# res-standalone.net
KiCad netlist of a schematic drawn in EAGLE
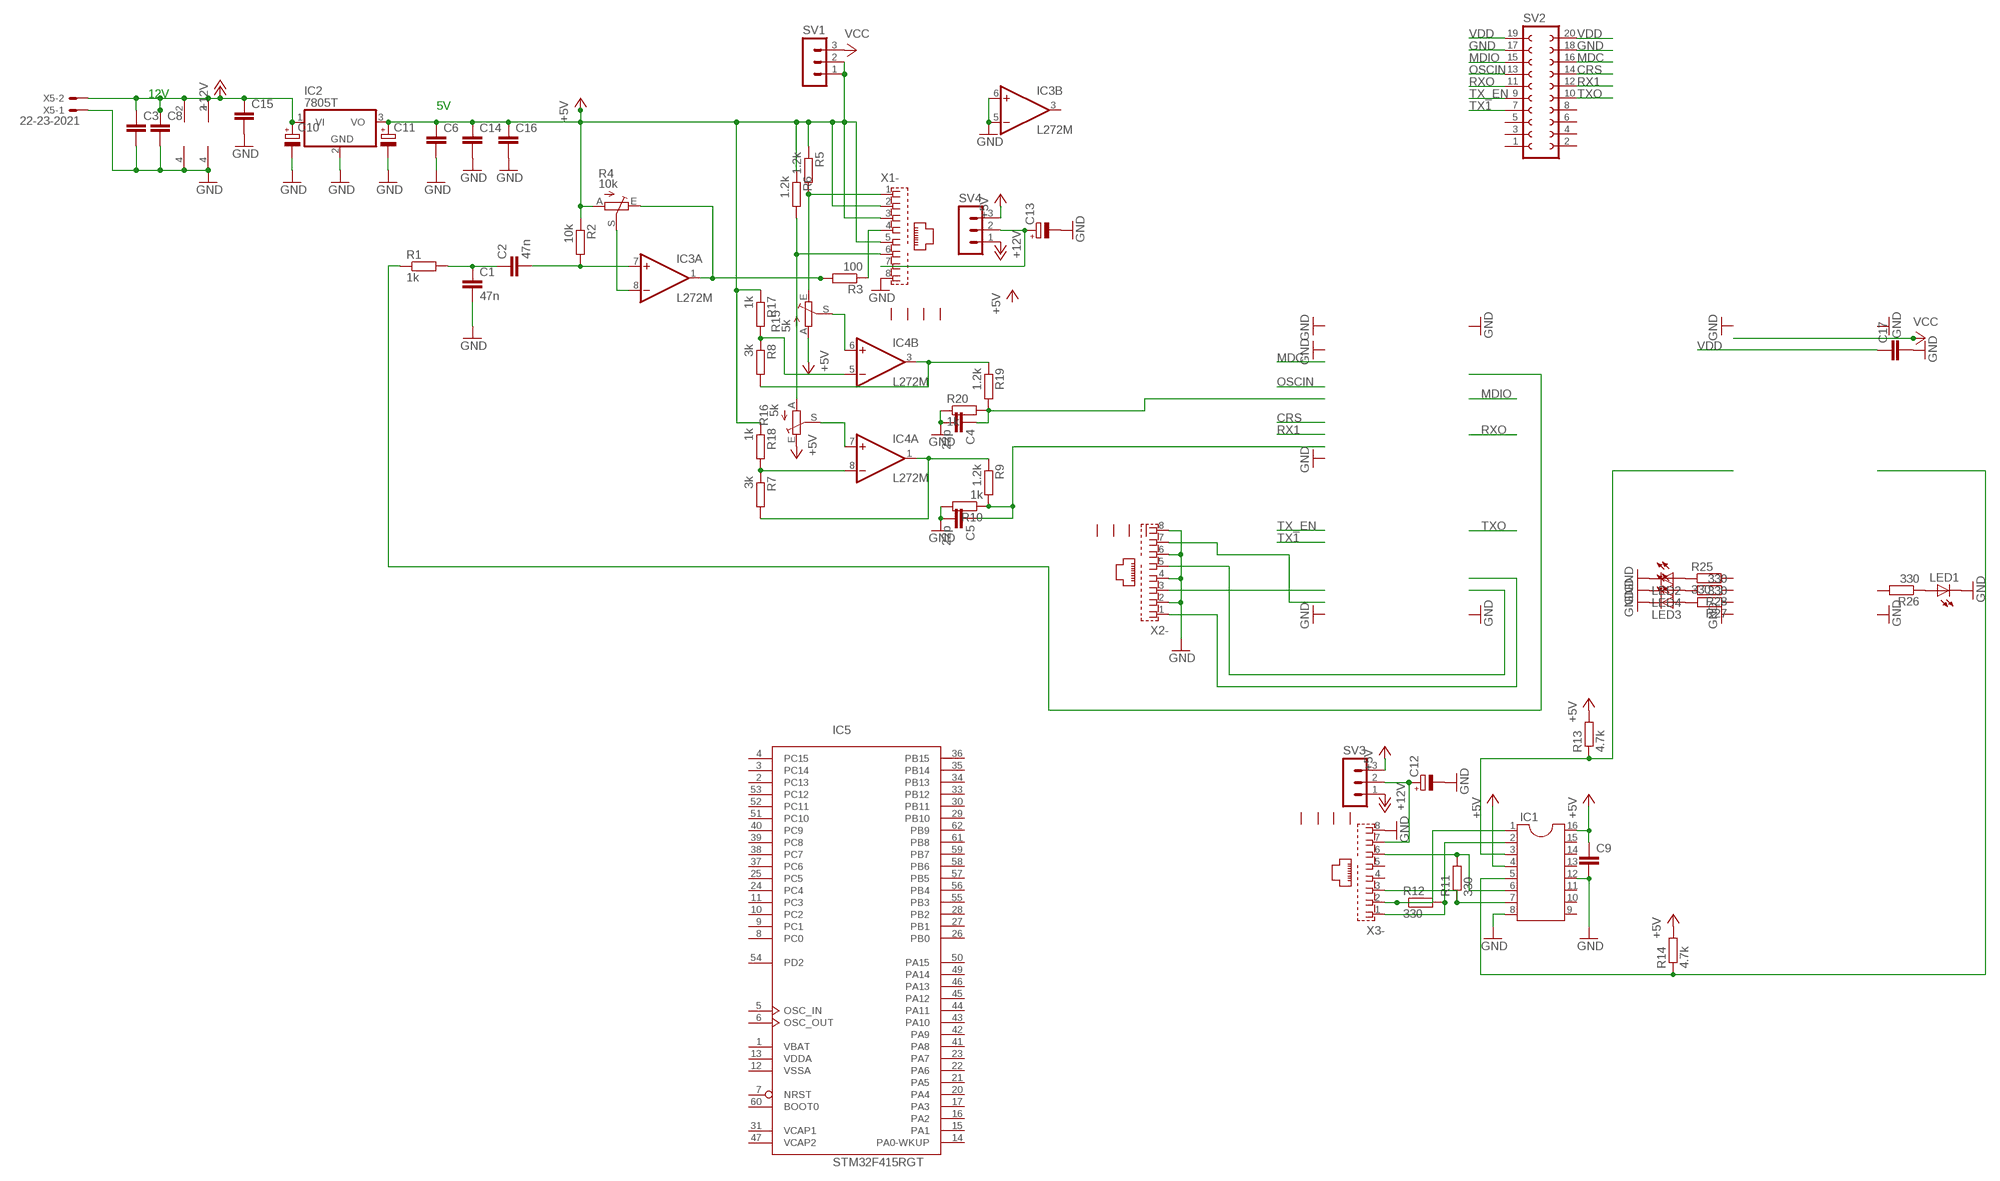
[diagram p0: schematic, sheet 1]

(export (version "E")
  (design (tool "Eeschema 10.0.6"))
  (components
    (comp (ref "C1")
      (value "47n")
      (footprint "eagle-import:C050-025X075")
      (libsource (lib "eagle-import") (part "C-EU050-025X075"))
    )
    (comp (ref "C2")
      (value "47n")
      (footprint "eagle-import:C050-025X075")
      (libsource (lib "eagle-import") (part "C-EU050-025X075"))
    )
    (comp (ref "C3")
      (value "C-EU050-025X075")
      (footprint "eagle-import:C050-025X075")
      (libsource (lib "eagle-import") (part "C-EU050-025X075"))
    )
    (comp (ref "C4")
      (value "22p")
      (footprint "eagle-import:C050-025X075")
      (libsource (lib "eagle-import") (part "C-EU050-025X075"))
    )
    (comp (ref "C5")
      (value "22p")
      (footprint "eagle-import:C050-025X075")
      (libsource (lib "eagle-import") (part "C-EU050-025X075"))
    )
    (comp (ref "C6")
      (value "C-EU050-025X075")
      (footprint "eagle-import:C050-025X075")
      (libsource (lib "eagle-import") (part "C-EU050-025X075"))
    )
    (comp (ref "C8")
      (value "C-EU050-025X075")
      (footprint "eagle-import:C050-025X075")
      (libsource (lib "eagle-import") (part "C-EU050-025X075"))
    )
    (comp (ref "C9")
      (value "C-EU050-025X075")
      (footprint "eagle-import:C050-025X075")
      (libsource (lib "eagle-import") (part "C-EU050-025X075"))
    )
    (comp (ref "C10")
      (value "CPOL-EUE2.5-5")
      (footprint "eagle-import:E2,5-5")
      (libsource (lib "eagle-import") (part "CPOL-EUE2.5-5"))
    )
    (comp (ref "C11")
      (value "CPOL-EUE2.5-5")
      (footprint "eagle-import:E2,5-5")
      (libsource (lib "eagle-import") (part "CPOL-EUE2.5-5"))
    )
    (comp (ref "C12")
      (value "CPOL-EUE2.5-5")
      (footprint "eagle-import:E2,5-5")
      (libsource (lib "eagle-import") (part "CPOL-EUE2.5-5"))
    )
    (comp (ref "C13")
      (value "CPOL-EUE2.5-5")
      (footprint "eagle-import:E2,5-5")
      (libsource (lib "eagle-import") (part "CPOL-EUE2.5-5"))
    )
    (comp (ref "C14")
      (value "C-EU050-025X075")
      (footprint "eagle-import:C050-025X075")
      (libsource (lib "eagle-import") (part "C-EU050-025X075"))
    )
    (comp (ref "C15")
      (value "C-EU050-025X075")
      (footprint "eagle-import:C050-025X075")
      (libsource (lib "eagle-import") (part "C-EU050-025X075"))
    )
    (comp (ref "C16")
      (value "C-EU050-025X075")
      (footprint "eagle-import:C050-025X075")
      (libsource (lib "eagle-import") (part "C-EU050-025X075"))
    )
    (comp (ref "C17")
      (value "C-EU050-025X075")
      (footprint "eagle-import:C050-025X075")
      (libsource (lib "eagle-import") (part "C-EU050-025X075"))
    )
    (comp (ref "IC1")
      (value "DIL16")
      (footprint "eagle-import:DIL16")
      (libsource (lib "eagle-import") (part "DIL16"))
    )
    (comp (ref "IC2")
      (value "7805T")
      (footprint "eagle-import:TO220H")
      (libsource (lib "eagle-import") (part "78T05"))
    )
    (comp (ref "IC3")
      (value "L272M")
      (footprint "eagle-import:DIL08")
      (libsource (lib "eagle-import") (part "L272M"))
    )
    (comp (ref "IC4")
      (value "L272M")
      (footprint "eagle-import:DIL08")
      (libsource (lib "eagle-import") (part "L272M"))
    )
    (comp (ref "IC5")
      (value "STM32F415RGT")
      (footprint "eagle-import:LQFP64")
      (libsource (lib "eagle-import") (part "STM32F415RTG"))
    )
    (comp (ref "LED1")
      (value "LED3MM")
      (footprint "eagle-import:LED3MM")
      (libsource (lib "eagle-import") (part "LED3MM"))
    )
    (comp (ref "LED2")
      (value "LED3MM")
      (footprint "eagle-import:LED3MM")
      (libsource (lib "eagle-import") (part "LED3MM"))
    )
    (comp (ref "LED3")
      (value "LED3MM")
      (footprint "eagle-import:LED3MM")
      (libsource (lib "eagle-import") (part "LED3MM"))
    )
    (comp (ref "LED4")
      (value "LED3MM")
      (footprint "eagle-import:LED3MM")
      (libsource (lib "eagle-import") (part "LED3MM"))
    )
    (comp (ref "R1")
      (value "1k")
      (footprint "eagle-import:0204_7")
      (libsource (lib "eagle-import") (part "R-EU_0204/7"))
    )
    (comp (ref "R2")
      (value "10k")
      (footprint "eagle-import:0204_7")
      (libsource (lib "eagle-import") (part "R-EU_0204/7"))
    )
    (comp (ref "R3")
      (value "100")
      (footprint "eagle-import:0204_7")
      (libsource (lib "eagle-import") (part "R-EU_0204/7"))
    )
    (comp (ref "R4")
      (value "10k")
      (footprint "eagle-import:CA6V")
      (libsource (lib "eagle-import") (part "TRIM_EU-CA6V"))
    )
    (comp (ref "R5")
      (value "1.2k")
      (footprint "eagle-import:0204_7")
      (libsource (lib "eagle-import") (part "R-EU_0204/7"))
    )
    (comp (ref "R6")
      (value "1.2k")
      (footprint "eagle-import:0204_7")
      (libsource (lib "eagle-import") (part "R-EU_0204/7"))
    )
    (comp (ref "R7")
      (value "3k")
      (footprint "eagle-import:0204_7")
      (libsource (lib "eagle-import") (part "R-EU_0204/7"))
    )
    (comp (ref "R8")
      (value "3k")
      (footprint "eagle-import:0204_7")
      (libsource (lib "eagle-import") (part "R-EU_0204/7"))
    )
    (comp (ref "R9")
      (value "1.2k")
      (footprint "eagle-import:0204_7")
      (libsource (lib "eagle-import") (part "R-EU_0204/7"))
    )
    (comp (ref "R10")
      (value "1k")
      (footprint "eagle-import:0204_7")
      (libsource (lib "eagle-import") (part "R-EU_0204/7"))
    )
    (comp (ref "R11")
      (value "330")
      (footprint "eagle-import:0204_7")
      (libsource (lib "eagle-import") (part "R-EU_0204/7"))
    )
    (comp (ref "R12")
      (value "330")
      (footprint "eagle-import:0204_7")
      (libsource (lib "eagle-import") (part "R-EU_0204/7"))
    )
    (comp (ref "R13")
      (value "4.7k")
      (footprint "eagle-import:0204_7")
      (libsource (lib "eagle-import") (part "R-EU_0204/7"))
    )
    (comp (ref "R14")
      (value "4.7k")
      (footprint "eagle-import:0204_7")
      (libsource (lib "eagle-import") (part "R-EU_0204/7"))
    )
    (comp (ref "R15")
      (value "5k")
      (footprint "eagle-import:CA6V")
      (libsource (lib "eagle-import") (part "TRIM_EU-CA6V"))
    )
    (comp (ref "R16")
      (value "5k")
      (footprint "eagle-import:CA6V")
      (libsource (lib "eagle-import") (part "TRIM_EU-CA6V"))
    )
    (comp (ref "R17")
      (value "1k")
      (footprint "eagle-import:0204_7")
      (libsource (lib "eagle-import") (part "R-EU_0204/7"))
    )
    (comp (ref "R18")
      (value "1k")
      (footprint "eagle-import:0204_7")
      (libsource (lib "eagle-import") (part "R-EU_0204/7"))
    )
    (comp (ref "R19")
      (value "1.2k")
      (footprint "eagle-import:0204_7")
      (libsource (lib "eagle-import") (part "R-EU_0204/7"))
    )
    (comp (ref "R20")
      (value "1k")
      (footprint "eagle-import:0204_7")
      (libsource (lib "eagle-import") (part "R-EU_0204/7"))
    )
    (comp (ref "R25")
      (value "330")
      (footprint "eagle-import:0204_7")
      (libsource (lib "eagle-import") (part "R-EU_0204/7"))
    )
    (comp (ref "R26")
      (value "330")
      (footprint "eagle-import:0204_7")
      (libsource (lib "eagle-import") (part "R-EU_0204/7"))
    )
    (comp (ref "R27")
      (value "330")
      (footprint "eagle-import:0204_7")
      (libsource (lib "eagle-import") (part "R-EU_0204/7"))
    )
    (comp (ref "R28")
      (value "330")
      (footprint "eagle-import:0204_7")
      (libsource (lib "eagle-import") (part "R-EU_0204/7"))
    )
    (comp (ref "SV1")
      (value "MA03-1")
      (footprint "eagle-import:MA03-1")
      (libsource (lib "eagle-import") (part "MA03-1"))
    )
    (comp (ref "SV2")
      (value "FE10-2W")
      (footprint "eagle-import:FE10-2W")
      (libsource (lib "eagle-import") (part "FE10-2W"))
    )
    (comp (ref "SV3")
      (value "MA03-1")
      (footprint "eagle-import:MA03-1")
      (libsource (lib "eagle-import") (part "MA03-1"))
    )
    (comp (ref "SV4")
      (value "MA03-1")
      (footprint "eagle-import:MA03-1")
      (libsource (lib "eagle-import") (part "MA03-1"))
    )
    (comp (ref "X1")
      (value "RJ45")
      (footprint "eagle-import:RJ45")
      (libsource (lib "eagle-import") (part "RJ45"))
    )
    (comp (ref "X2")
      (value "RJ45")
      (footprint "eagle-import:RJ45")
      (libsource (lib "eagle-import") (part "RJ45"))
    )
    (comp (ref "X3")
      (value "RJ45")
      (footprint "eagle-import:RJ45")
      (libsource (lib "eagle-import") (part "RJ45"))
    )
    (comp (ref "X5")
      (value "22-23-2021")
      (footprint "eagle-import:22-23-2021")
      (fields (field (name "MF") "MOLEX"))
      (libsource (lib "eagle-import") (part "22-23-2021"))
    )
  )
  (nets
    (net (code "1") (name "+5V") (class "Default")
      (node (ref "C11") (pin "+") (pinfunction "+_+") (pintype "passive"))
      (node (ref "C14") (pin "1") (pinfunction "1_1") (pintype "passive"))
      (node (ref "C16") (pin "1") (pinfunction "1_1") (pintype "passive"))
      (node (ref "C6") (pin "1") (pinfunction "1_1") (pintype "passive"))
      (node (ref "C9") (pin "1") (pinfunction "1_1") (pintype "passive"))
      (node (ref "IC1") (pin "16") (pinfunction "16_16") (pintype "passive"))
      (node (ref "IC1") (pin "4") (pinfunction "4_4") (pintype "passive"))
      (node (ref "IC2") (pin "3") (pinfunction "VO_3") (pintype "passive"))
      (node (ref "R13") (pin "2") (pinfunction "2_2") (pintype "passive"))
      (node (ref "R14") (pin "2") (pinfunction "2_2") (pintype "passive"))
      (node (ref "R15") (pin "A") (pinfunction "A_A") (pintype "passive"))
      (node (ref "R16") (pin "E") (pinfunction "E_E") (pintype "passive"))
      (node (ref "R17") (pin "1") (pinfunction "1_1") (pintype "passive"))
      (node (ref "R18") (pin "1") (pinfunction "1_1") (pintype "passive"))
      (node (ref "R2") (pin "1") (pinfunction "1_1") (pintype "passive"))
      (node (ref "R4") (pin "A") (pinfunction "A_A") (pintype "passive"))
      (node (ref "R5") (pin "1") (pinfunction "1_1") (pintype "passive"))
      (node (ref "R6") (pin "1") (pinfunction "1_1") (pintype "passive"))
      (node (ref "SV1") (pin "1") (pinfunction "1_1") (pintype "passive"))
      (node (ref "SV1") (pin "2") (pinfunction "2_2") (pintype "passive"))
      (node (ref "SV3") (pin "3") (pinfunction "3_3") (pintype "passive"))
      (node (ref "SV4") (pin "3") (pinfunction "3_3") (pintype "passive"))
      (node (ref "X1") (pin "2") (pinfunction "2_2") (pintype "passive"))
      (node (ref "X1") (pin "3") (pinfunction "3_3") (pintype "passive"))
      (node (ref "X1") (pin "5") (pinfunction "5_5") (pintype "passive"))
    )
    (net (code "2") (name "+12V") (class "Default")
      (node (ref "C10") (pin "+") (pinfunction "+_+") (pintype "passive"))
      (node (ref "C15") (pin "1") (pinfunction "1_1") (pintype "passive"))
      (node (ref "C3") (pin "1") (pinfunction "1_1") (pintype "passive"))
      (node (ref "C8") (pin "1") (pinfunction "1_1") (pintype "passive"))
      (node (ref "IC2") (pin "1") (pinfunction "VI_1") (pintype "input"))
      (node (ref "IC3") (pin "2") (pinfunction "V+_2") (pintype "power_in"))
      (node (ref "IC4") (pin "2") (pinfunction "V+_2") (pintype "power_in"))
      (node (ref "SV3") (pin "1") (pinfunction "1_1") (pintype "passive"))
      (node (ref "SV4") (pin "1") (pinfunction "1_1") (pintype "passive"))
      (node (ref "X5") (pin "2") (pinfunction "S_2") (pintype "passive"))
    )
    (net (code "3") (name "/CRS") (class "Default")
      (node (ref "SV2") (pin "14") (pinfunction "14_14") (pintype "passive"))
    )
    (net (code "4") (name "/MDC") (class "Default")
      (node (ref "SV2") (pin "16") (pinfunction "16_16") (pintype "passive"))
    )
    (net (code "5") (name "/MDIO") (class "Default")
      (node (ref "SV2") (pin "15") (pinfunction "15_15") (pintype "passive"))
    )
    (net (code "6") (name "/OSCIN") (class "Default")
      (node (ref "SV2") (pin "13") (pinfunction "13_13") (pintype "passive"))
    )
    (net (code "7") (name "/RX1") (class "Default")
      (node (ref "SV2") (pin "12") (pinfunction "12_12") (pintype "passive"))
    )
    (net (code "8") (name "/RXO") (class "Default")
      (node (ref "SV2") (pin "11") (pinfunction "11_11") (pintype "passive"))
    )
    (net (code "9") (name "/TX1") (class "Default")
      (node (ref "SV2") (pin "7") (pinfunction "7_7") (pintype "passive"))
    )
    (net (code "10") (name "/TXO") (class "Default")
      (node (ref "SV2") (pin "10") (pinfunction "10_10") (pintype "passive"))
    )
    (net (code "11") (name "/TX_EN") (class "Default")
      (node (ref "SV2") (pin "9") (pinfunction "9_9") (pintype "passive"))
    )
    (net (code "12") (name "/VBAT") (class "Default")
      (node (ref "IC5") (pin "1") (pinfunction "VBAT_1") (pintype "power_in"))
    )
    (net (code "13") (name "/VCAP1") (class "Default")
      (node (ref "IC5") (pin "31") (pinfunction "VCAP1_31") (pintype "power_in"))
    )
    (net (code "14") (name "/VCAP2") (class "Default")
      (node (ref "IC5") (pin "47") (pinfunction "VCAP2_47") (pintype "power_in"))
    )
    (net (code "15") (name "/VDD") (class "Default")
      (node (ref "C17") (pin "1") (pinfunction "1_1") (pintype "passive"))
      (node (ref "SV2") (pin "19") (pinfunction "19_19") (pintype "passive"))
      (node (ref "SV2") (pin "20") (pinfunction "20_20") (pintype "passive"))
    )
    (net (code "16") (name "/VDDA") (class "Default")
      (node (ref "IC5") (pin "13") (pinfunction "VDDA_13") (pintype "power_in"))
    )
    (net (code "17") (name "/VSSA") (class "Default")
      (node (ref "IC5") (pin "12") (pinfunction "VSSA_12") (pintype "power_in"))
    )
    (net (code "18") (name "GND") (class "Default")
      (node (ref "C1") (pin "2") (pinfunction "2_2") (pintype "passive"))
      (node (ref "C10") (pin "-") (pinfunction "-_-") (pintype "passive"))
      (node (ref "C11") (pin "-") (pinfunction "-_-") (pintype "passive"))
      (node (ref "C12") (pin "-") (pinfunction "-_-") (pintype "passive"))
      (node (ref "C13") (pin "-") (pinfunction "-_-") (pintype "passive"))
      (node (ref "C14") (pin "2") (pinfunction "2_2") (pintype "passive"))
      (node (ref "C15") (pin "2") (pinfunction "2_2") (pintype "passive"))
      (node (ref "C16") (pin "2") (pinfunction "2_2") (pintype "passive"))
      (node (ref "C17") (pin "2") (pinfunction "2_2") (pintype "passive"))
      (node (ref "C3") (pin "2") (pinfunction "2_2") (pintype "passive"))
      (node (ref "C4") (pin "2") (pinfunction "2_2") (pintype "passive"))
      (node (ref "C5") (pin "2") (pinfunction "2_2") (pintype "passive"))
      (node (ref "C6") (pin "2") (pinfunction "2_2") (pintype "passive"))
      (node (ref "C8") (pin "2") (pinfunction "2_2") (pintype "passive"))
      (node (ref "C9") (pin "2") (pinfunction "2_2") (pintype "passive"))
      (node (ref "IC1") (pin "12") (pinfunction "12_12") (pintype "passive"))
      (node (ref "IC1") (pin "8") (pinfunction "8_8") (pintype "passive"))
      (node (ref "IC2") (pin "2") (pinfunction "GND_2") (pintype "passive"))
      (node (ref "IC3") (pin "4") (pinfunction "GND_4") (pintype "power_in"))
      (node (ref "IC3") (pin "5") (pinfunction "-IN_5") (pintype "input"))
      (node (ref "IC3") (pin "6") (pinfunction "+IN_6") (pintype "input"))
      (node (ref "IC4") (pin "4") (pinfunction "GND_4") (pintype "power_in"))
      (node (ref "LED1") (pin "K") (pinfunction "C_K") (pintype "passive"))
      (node (ref "LED2") (pin "K") (pinfunction "C_K") (pintype "passive"))
      (node (ref "LED3") (pin "K") (pinfunction "C_K") (pintype "passive"))
      (node (ref "LED4") (pin "K") (pinfunction "C_K") (pintype "passive"))
      (node (ref "R10") (pin "2") (pinfunction "2_2") (pintype "passive"))
      (node (ref "R20") (pin "1") (pinfunction "1_1") (pintype "passive"))
      (node (ref "SV2") (pin "17") (pinfunction "17_17") (pintype "passive"))
      (node (ref "SV2") (pin "18") (pinfunction "18_18") (pintype "passive"))
      (node (ref "X1") (pin "8") (pinfunction "8_8") (pintype "passive"))
      (node (ref "X2") (pin "2") (pinfunction "2_2") (pintype "passive"))
      (node (ref "X2") (pin "4") (pinfunction "4_4") (pintype "passive"))
      (node (ref "X2") (pin "6") (pinfunction "6_6") (pintype "passive"))
      (node (ref "X2") (pin "8") (pinfunction "8_8") (pintype "passive"))
      (node (ref "X3") (pin "8") (pinfunction "8_8") (pintype "passive"))
      (node (ref "X5") (pin "1") (pinfunction "S_1") (pintype "passive"))
    )
    (net (code "19") (name "Net-(C1-Pad1)") (class "Default")
      (node (ref "C1") (pin "1") (pinfunction "1_1") (pintype "passive"))
      (node (ref "C2") (pin "1") (pinfunction "1_1") (pintype "passive"))
      (node (ref "R1") (pin "2") (pinfunction "2_2") (pintype "passive"))
    )
    (net (code "20") (name "Net-(C4-Pad1)") (class "Default")
      (node (ref "C4") (pin "1") (pinfunction "1_1") (pintype "passive"))
      (node (ref "R19") (pin "2") (pinfunction "2_2") (pintype "passive"))
      (node (ref "R20") (pin "2") (pinfunction "2_2") (pintype "passive"))
    )
    (net (code "21") (name "Net-(C5-Pad1)") (class "Default")
      (node (ref "C5") (pin "1") (pinfunction "1_1") (pintype "passive"))
      (node (ref "R10") (pin "1") (pinfunction "1_1") (pintype "passive"))
      (node (ref "R9") (pin "2") (pinfunction "2_2") (pintype "passive"))
    )
    (net (code "22") (name "Net-(C12-Pad+)") (class "Default")
      (node (ref "C12") (pin "+") (pinfunction "+_+") (pintype "passive"))
      (node (ref "SV3") (pin "2") (pinfunction "2_2") (pintype "passive"))
      (node (ref "X3") (pin "7") (pinfunction "7_7") (pintype "passive"))
    )
    (net (code "23") (name "Net-(C13-Pad+)") (class "Default")
      (node (ref "C13") (pin "+") (pinfunction "+_+") (pintype "passive"))
      (node (ref "SV4") (pin "2") (pinfunction "2_2") (pintype "passive"))
      (node (ref "X1") (pin "7") (pinfunction "7_7") (pintype "passive"))
    )
    (net (code "24") (name "Net-(IC1-Pad1)") (class "Default")
      (node (ref "IC1") (pin "1") (pinfunction "1_1") (pintype "passive"))
      (node (ref "R12") (pin "1") (pinfunction "1_1") (pintype "passive"))
      (node (ref "X3") (pin "2") (pinfunction "2_2") (pintype "passive"))
    )
    (net (code "25") (name "Net-(IC1-Pad2)") (class "Default")
      (node (ref "IC1") (pin "2") (pinfunction "2_2") (pintype "passive"))
      (node (ref "R12") (pin "2") (pinfunction "2_2") (pintype "passive"))
      (node (ref "X3") (pin "1") (pinfunction "1_1") (pintype "passive"))
    )
    (net (code "26") (name "Net-(IC1-Pad3)") (class "Default")
      (node (ref "IC1") (pin "3") (pinfunction "3_3") (pintype "passive"))
      (node (ref "R13") (pin "1") (pinfunction "1_1") (pintype "passive"))
    )
    (net (code "27") (name "Net-(IC1-Pad5)") (class "Default")
      (node (ref "IC1") (pin "5") (pinfunction "5_5") (pintype "passive"))
      (node (ref "R14") (pin "1") (pinfunction "1_1") (pintype "passive"))
    )
    (net (code "28") (name "Net-(IC1-Pad6)") (class "Default")
      (node (ref "IC1") (pin "6") (pinfunction "6_6") (pintype "passive"))
      (node (ref "R11") (pin "2") (pinfunction "2_2") (pintype "passive"))
      (node (ref "X3") (pin "6") (pinfunction "6_6") (pintype "passive"))
    )
    (net (code "29") (name "Net-(IC1-Pad7)") (class "Default")
      (node (ref "IC1") (pin "7") (pinfunction "7_7") (pintype "passive"))
      (node (ref "R11") (pin "1") (pinfunction "1_1") (pintype "passive"))
      (node (ref "X3") (pin "3") (pinfunction "3_3") (pintype "passive"))
    )
    (net (code "30") (name "Net-(IC3A-+IN)") (class "Default")
      (node (ref "C2") (pin "2") (pinfunction "2_2") (pintype "passive"))
      (node (ref "IC3") (pin "7") (pinfunction "+IN_7") (pintype "input"))
      (node (ref "R2") (pin "2") (pinfunction "2_2") (pintype "passive"))
    )
    (net (code "31") (name "Net-(IC3A--IN)") (class "Default")
      (node (ref "IC3") (pin "8") (pinfunction "-IN_8") (pintype "input"))
      (node (ref "R4") (pin "S") (pinfunction "S_S") (pintype "passive"))
    )
    (net (code "32") (name "Net-(IC3A-OUT)") (class "Default")
      (node (ref "IC3") (pin "1") (pinfunction "OUT_1") (pintype "output"))
      (node (ref "R3") (pin "2") (pinfunction "2_2") (pintype "passive"))
      (node (ref "R4") (pin "E") (pinfunction "E_E") (pintype "passive"))
    )
    (net (code "33") (name "Net-(IC4A-+IN)") (class "Default")
      (node (ref "IC4") (pin "7") (pinfunction "+IN_7") (pintype "input"))
      (node (ref "R16") (pin "S") (pinfunction "S_S") (pintype "passive"))
    )
    (net (code "34") (name "Net-(IC4A--IN)") (class "Default")
      (node (ref "IC4") (pin "8") (pinfunction "-IN_8") (pintype "input"))
      (node (ref "R18") (pin "2") (pinfunction "2_2") (pintype "passive"))
      (node (ref "R7") (pin "1") (pinfunction "1_1") (pintype "passive"))
    )
    (net (code "35") (name "Net-(IC4A-OUT)") (class "Default")
      (node (ref "IC4") (pin "1") (pinfunction "OUT_1") (pintype "output"))
      (node (ref "R7") (pin "2") (pinfunction "2_2") (pintype "passive"))
      (node (ref "R9") (pin "1") (pinfunction "1_1") (pintype "passive"))
    )
    (net (code "36") (name "Net-(IC4B-+IN)") (class "Default")
      (node (ref "IC4") (pin "6") (pinfunction "+IN_6") (pintype "input"))
      (node (ref "R15") (pin "S") (pinfunction "S_S") (pintype "passive"))
    )
    (net (code "37") (name "Net-(IC4B--IN)") (class "Default")
      (node (ref "IC4") (pin "5") (pinfunction "-IN_5") (pintype "input"))
      (node (ref "R17") (pin "2") (pinfunction "2_2") (pintype "passive"))
      (node (ref "R8") (pin "1") (pinfunction "1_1") (pintype "passive"))
    )
    (net (code "38") (name "Net-(IC4B-OUT)") (class "Default")
      (node (ref "IC4") (pin "3") (pinfunction "OUT_3") (pintype "output"))
      (node (ref "R19") (pin "1") (pinfunction "1_1") (pintype "passive"))
      (node (ref "R8") (pin "2") (pinfunction "2_2") (pintype "passive"))
    )
    (net (code "39") (name "Net-(LED1-PadA)") (class "Default")
      (node (ref "LED1") (pin "A") (pinfunction "A_A") (pintype "passive"))
      (node (ref "R26") (pin "1") (pinfunction "1_1") (pintype "passive"))
    )
    (net (code "40") (name "Net-(LED2-PadA)") (class "Default")
      (node (ref "LED2") (pin "A") (pinfunction "A_A") (pintype "passive"))
      (node (ref "R25") (pin "1") (pinfunction "1_1") (pintype "passive"))
    )
    (net (code "41") (name "Net-(LED3-PadA)") (class "Default")
      (node (ref "LED3") (pin "A") (pinfunction "A_A") (pintype "passive"))
      (node (ref "R27") (pin "2") (pinfunction "2_2") (pintype "passive"))
    )
    (net (code "42") (name "Net-(LED4-PadA)") (class "Default")
      (node (ref "LED4") (pin "A") (pinfunction "A_A") (pintype "passive"))
      (node (ref "R28") (pin "2") (pinfunction "2_2") (pintype "passive"))
    )
    (net (code "43") (name "Net-(R3-Pad1)") (class "Default")
      (node (ref "R3") (pin "1") (pinfunction "1_1") (pintype "passive"))
      (node (ref "X1") (pin "4") (pinfunction "4_4") (pintype "passive"))
    )
    (net (code "44") (name "Net-(R15-PadE)") (class "Default")
      (node (ref "R15") (pin "E") (pinfunction "E_E") (pintype "passive"))
      (node (ref "R5") (pin "2") (pinfunction "2_2") (pintype "passive"))
      (node (ref "X1") (pin "1") (pinfunction "1_1") (pintype "passive"))
    )
    (net (code "45") (name "Net-(R16-PadA)") (class "Default")
      (node (ref "R16") (pin "A") (pinfunction "A_A") (pintype "passive"))
      (node (ref "R6") (pin "2") (pinfunction "2_2") (pintype "passive"))
      (node (ref "X1") (pin "6") (pinfunction "6_6") (pintype "passive"))
    )
    (net (code "46") (name "VCC") (class "Default")
      (node (ref "SV1") (pin "3") (pinfunction "3_3") (pintype "passive"))
    )
    (net (code "47") (name "unconnected-(IC1-Pad9)") (class "Default")
      (node (ref "IC1") (pin "9") (pinfunction "9_9") (pintype "passive"))
    )
    (net (code "48") (name "unconnected-(IC1-Pad10)") (class "Default")
      (node (ref "IC1") (pin "10") (pinfunction "10_10") (pintype "passive"))
    )
    (net (code "49") (name "unconnected-(IC1-Pad11)") (class "Default")
      (node (ref "IC1") (pin "11") (pinfunction "11_11") (pintype "passive"))
    )
    (net (code "50") (name "unconnected-(IC1-Pad13)") (class "Default")
      (node (ref "IC1") (pin "13") (pinfunction "13_13") (pintype "passive"))
    )
    (net (code "51") (name "unconnected-(IC1-Pad14)") (class "Default")
      (node (ref "IC1") (pin "14") (pinfunction "14_14") (pintype "passive"))
    )
    (net (code "52") (name "unconnected-(IC1-Pad15)") (class "Default")
      (node (ref "IC1") (pin "15") (pinfunction "15_15") (pintype "passive"))
    )
    (net (code "53") (name "unconnected-(IC3B-OUT-Pad3)") (class "Default")
      (node (ref "IC3") (pin "3") (pinfunction "OUT_3") (pintype "output"))
    )
    (net (code "54") (name "unconnected-(IC5A-BOOT0-Pad60)") (class "Default")
      (node (ref "IC5") (pin "60") (pinfunction "BOOT0_60") (pintype "input"))
    )
    (net (code "55") (name "unconnected-(IC5A-NRST-Pad7)") (class "Default")
      (node (ref "IC5") (pin "7") (pinfunction "NRST_7") (pintype "bidirectional"))
    )
    (net (code "56") (name "unconnected-(IC5A-OSC_IN-Pad5)") (class "Default")
      (node (ref "IC5") (pin "5") (pinfunction "OSC_IN_5") (pintype "bidirectional"))
    )
    (net (code "57") (name "unconnected-(IC5A-OSC_OUT-Pad6)") (class "Default")
      (node (ref "IC5") (pin "6") (pinfunction "OSC_OUT_6") (pintype "bidirectional"))
    )
    (net (code "58") (name "unconnected-(IC5A-PA0-WKUP-Pad14)") (class "Default")
      (node (ref "IC5") (pin "14") (pinfunction "PA0-WKUP_14") (pintype "bidirectional"))
    )
    (net (code "59") (name "unconnected-(IC5A-PA1-Pad15)") (class "Default")
      (node (ref "IC5") (pin "15") (pinfunction "PA1_15") (pintype "bidirectional"))
    )
    (net (code "60") (name "unconnected-(IC5A-PA2-Pad16)") (class "Default")
      (node (ref "IC5") (pin "16") (pinfunction "PA2_16") (pintype "bidirectional"))
    )
    (net (code "61") (name "unconnected-(IC5A-PA3-Pad17)") (class "Default")
      (node (ref "IC5") (pin "17") (pinfunction "PA3_17") (pintype "bidirectional"))
    )
    (net (code "62") (name "unconnected-(IC5A-PA4-Pad20)") (class "Default")
      (node (ref "IC5") (pin "20") (pinfunction "PA4_20") (pintype "bidirectional"))
    )
    (net (code "63") (name "unconnected-(IC5A-PA5-Pad21)") (class "Default")
      (node (ref "IC5") (pin "21") (pinfunction "PA5_21") (pintype "bidirectional"))
    )
    (net (code "64") (name "unconnected-(IC5A-PA6-Pad22)") (class "Default")
      (node (ref "IC5") (pin "22") (pinfunction "PA6_22") (pintype "bidirectional"))
    )
    (net (code "65") (name "unconnected-(IC5A-PA7-Pad23)") (class "Default")
      (node (ref "IC5") (pin "23") (pinfunction "PA7_23") (pintype "bidirectional"))
    )
    (net (code "66") (name "unconnected-(IC5A-PA8-Pad41)") (class "Default")
      (node (ref "IC5") (pin "41") (pinfunction "PA8_41") (pintype "bidirectional"))
    )
    (net (code "67") (name "unconnected-(IC5A-PA9-Pad42)") (class "Default")
      (node (ref "IC5") (pin "42") (pinfunction "PA9_42") (pintype "bidirectional"))
    )
    (net (code "68") (name "unconnected-(IC5A-PA10-Pad43)") (class "Default")
      (node (ref "IC5") (pin "43") (pinfunction "PA10_43") (pintype "bidirectional"))
    )
    (net (code "69") (name "unconnected-(IC5A-PA11-Pad44)") (class "Default")
      (node (ref "IC5") (pin "44") (pinfunction "PA11_44") (pintype "bidirectional"))
    )
    (net (code "70") (name "unconnected-(IC5A-PA12-Pad45)") (class "Default")
      (node (ref "IC5") (pin "45") (pinfunction "PA12_45") (pintype "bidirectional"))
    )
    (net (code "71") (name "unconnected-(IC5A-PA13-Pad46)") (class "Default")
      (node (ref "IC5") (pin "46") (pinfunction "PA13_46") (pintype "bidirectional"))
    )
    (net (code "72") (name "unconnected-(IC5A-PA14-Pad49)") (class "Default")
      (node (ref "IC5") (pin "49") (pinfunction "PA14_49") (pintype "bidirectional"))
    )
    (net (code "73") (name "unconnected-(IC5A-PA15-Pad50)") (class "Default")
      (node (ref "IC5") (pin "50") (pinfunction "PA15_50") (pintype "bidirectional"))
    )
    (net (code "74") (name "unconnected-(IC5A-PB0-Pad26)") (class "Default")
      (node (ref "IC5") (pin "26") (pinfunction "PB0_26") (pintype "bidirectional"))
    )
    (net (code "75") (name "unconnected-(IC5A-PB1-Pad27)") (class "Default")
      (node (ref "IC5") (pin "27") (pinfunction "PB1_27") (pintype "bidirectional"))
    )
    (net (code "76") (name "unconnected-(IC5A-PB2-Pad28)") (class "Default")
      (node (ref "IC5") (pin "28") (pinfunction "PB2_28") (pintype "bidirectional"))
    )
    (net (code "77") (name "unconnected-(IC5A-PB3-Pad55)") (class "Default")
      (node (ref "IC5") (pin "55") (pinfunction "PB3_55") (pintype "bidirectional"))
    )
    (net (code "78") (name "unconnected-(IC5A-PB4-Pad56)") (class "Default")
      (node (ref "IC5") (pin "56") (pinfunction "PB4_56") (pintype "bidirectional"))
    )
    (net (code "79") (name "unconnected-(IC5A-PB5-Pad57)") (class "Default")
      (node (ref "IC5") (pin "57") (pinfunction "PB5_57") (pintype "bidirectional"))
    )
    (net (code "80") (name "unconnected-(IC5A-PB6-Pad58)") (class "Default")
      (node (ref "IC5") (pin "58") (pinfunction "PB6_58") (pintype "bidirectional"))
    )
    (net (code "81") (name "unconnected-(IC5A-PB7-Pad59)") (class "Default")
      (node (ref "IC5") (pin "59") (pinfunction "PB7_59") (pintype "bidirectional"))
    )
    (net (code "82") (name "unconnected-(IC5A-PB8-Pad61)") (class "Default")
      (node (ref "IC5") (pin "61") (pinfunction "PB8_61") (pintype "bidirectional"))
    )
    (net (code "83") (name "unconnected-(IC5A-PB9-Pad62)") (class "Default")
      (node (ref "IC5") (pin "62") (pinfunction "PB9_62") (pintype "bidirectional"))
    )
    (net (code "84") (name "unconnected-(IC5A-PB10-Pad29)") (class "Default")
      (node (ref "IC5") (pin "29") (pinfunction "PB10_29") (pintype "bidirectional"))
    )
    (net (code "85") (name "unconnected-(IC5A-PB11-Pad30)") (class "Default")
      (node (ref "IC5") (pin "30") (pinfunction "PB11_30") (pintype "bidirectional"))
    )
    (net (code "86") (name "unconnected-(IC5A-PB12-Pad33)") (class "Default")
      (node (ref "IC5") (pin "33") (pinfunction "PB12_33") (pintype "bidirectional"))
    )
    (net (code "87") (name "unconnected-(IC5A-PB13-Pad34)") (class "Default")
      (node (ref "IC5") (pin "34") (pinfunction "PB13_34") (pintype "bidirectional"))
    )
    (net (code "88") (name "unconnected-(IC5A-PB14-Pad35)") (class "Default")
      (node (ref "IC5") (pin "35") (pinfunction "PB14_35") (pintype "bidirectional"))
    )
    (net (code "89") (name "unconnected-(IC5A-PB15-Pad36)") (class "Default")
      (node (ref "IC5") (pin "36") (pinfunction "PB15_36") (pintype "bidirectional"))
    )
    (net (code "90") (name "unconnected-(IC5A-PC0-Pad8)") (class "Default")
      (node (ref "IC5") (pin "8") (pinfunction "PC0_8") (pintype "bidirectional"))
    )
    (net (code "91") (name "unconnected-(IC5A-PC1-Pad9)") (class "Default")
      (node (ref "IC5") (pin "9") (pinfunction "PC1_9") (pintype "bidirectional"))
    )
    (net (code "92") (name "unconnected-(IC5A-PC2-Pad10)") (class "Default")
      (node (ref "IC5") (pin "10") (pinfunction "PC2_10") (pintype "bidirectional"))
    )
    (net (code "93") (name "unconnected-(IC5A-PC3-Pad11)") (class "Default")
      (node (ref "IC5") (pin "11") (pinfunction "PC3_11") (pintype "bidirectional"))
    )
    (net (code "94") (name "unconnected-(IC5A-PC4-Pad24)") (class "Default")
      (node (ref "IC5") (pin "24") (pinfunction "PC4_24") (pintype "bidirectional"))
    )
    (net (code "95") (name "unconnected-(IC5A-PC5-Pad25)") (class "Default")
      (node (ref "IC5") (pin "25") (pinfunction "PC5_25") (pintype "bidirectional"))
    )
    (net (code "96") (name "unconnected-(IC5A-PC6-Pad37)") (class "Default")
      (node (ref "IC5") (pin "37") (pinfunction "PC6_37") (pintype "bidirectional"))
    )
    (net (code "97") (name "unconnected-(IC5A-PC7-Pad38)") (class "Default")
      (node (ref "IC5") (pin "38") (pinfunction "PC7_38") (pintype "bidirectional"))
    )
    (net (code "98") (name "unconnected-(IC5A-PC8-Pad39)") (class "Default")
      (node (ref "IC5") (pin "39") (pinfunction "PC8_39") (pintype "bidirectional"))
    )
    (net (code "99") (name "unconnected-(IC5A-PC9-Pad40)") (class "Default")
      (node (ref "IC5") (pin "40") (pinfunction "PC9_40") (pintype "bidirectional"))
    )
    (net (code "100") (name "unconnected-(IC5A-PC10-Pad51)") (class "Default")
      (node (ref "IC5") (pin "51") (pinfunction "PC10_51") (pintype "bidirectional"))
    )
    (net (code "101") (name "unconnected-(IC5A-PC11-Pad52)") (class "Default")
      (node (ref "IC5") (pin "52") (pinfunction "PC11_52") (pintype "bidirectional"))
    )
    (net (code "102") (name "unconnected-(IC5A-PC12-Pad53)") (class "Default")
      (node (ref "IC5") (pin "53") (pinfunction "PC12_53") (pintype "bidirectional"))
    )
    (net (code "103") (name "unconnected-(IC5A-PC13-Pad2)") (class "Default")
      (node (ref "IC5") (pin "2") (pinfunction "PC13_2") (pintype "bidirectional"))
    )
    (net (code "104") (name "unconnected-(IC5A-PC14-Pad3)") (class "Default")
      (node (ref "IC5") (pin "3") (pinfunction "PC14_3") (pintype "bidirectional"))
    )
    (net (code "105") (name "unconnected-(IC5A-PC15-Pad4)") (class "Default")
      (node (ref "IC5") (pin "4") (pinfunction "PC15_4") (pintype "bidirectional"))
    )
    (net (code "106") (name "unconnected-(IC5A-PD2-Pad54)") (class "Default")
      (node (ref "IC5") (pin "54") (pinfunction "PD2_54") (pintype "bidirectional"))
    )
    (net (code "107") (name "unconnected-(R1-Pad1)") (class "Default")
      (node (ref "R1") (pin "1") (pinfunction "1_1") (pintype "passive"))
    )
    (net (code "108") (name "unconnected-(R25-Pad2)") (class "Default")
      (node (ref "R25") (pin "2") (pinfunction "2_2") (pintype "passive"))
    )
    (net (code "109") (name "unconnected-(R26-Pad2)") (class "Default")
      (node (ref "R26") (pin "2") (pinfunction "2_2") (pintype "passive"))
    )
    (net (code "110") (name "unconnected-(R27-Pad1)") (class "Default")
      (node (ref "R27") (pin "1") (pinfunction "1_1") (pintype "passive"))
    )
    (net (code "111") (name "unconnected-(R28-Pad1)") (class "Default")
      (node (ref "R28") (pin "1") (pinfunction "1_1") (pintype "passive"))
    )
    (net (code "112") (name "unconnected-(SV2-Pad1)") (class "Default")
      (node (ref "SV2") (pin "1") (pinfunction "1_1") (pintype "passive"))
    )
    (net (code "113") (name "unconnected-(SV2-Pad2)") (class "Default")
      (node (ref "SV2") (pin "2") (pinfunction "2_2") (pintype "passive"))
    )
    (net (code "114") (name "unconnected-(SV2-Pad3)") (class "Default")
      (node (ref "SV2") (pin "3") (pinfunction "3_3") (pintype "passive"))
    )
    (net (code "115") (name "unconnected-(SV2-Pad4)") (class "Default")
      (node (ref "SV2") (pin "4") (pinfunction "4_4") (pintype "passive"))
    )
    (net (code "116") (name "unconnected-(SV2-Pad5)") (class "Default")
      (node (ref "SV2") (pin "5") (pinfunction "5_5") (pintype "passive"))
    )
    (net (code "117") (name "unconnected-(SV2-Pad6)") (class "Default")
      (node (ref "SV2") (pin "6") (pinfunction "6_6") (pintype "passive"))
    )
    (net (code "118") (name "unconnected-(SV2-Pad8)") (class "Default")
      (node (ref "SV2") (pin "8") (pinfunction "8_8") (pintype "passive"))
    )
    (net (code "119") (name "unconnected-(X1B-1-PadG1)") (class "Default")
      (node (ref "X1") (pin "G1") (pinfunction "1_G1") (pintype "passive"))
    )
    (net (code "120") (name "unconnected-(X1C-1-PadG2)") (class "Default")
      (node (ref "X1") (pin "G2") (pinfunction "1_G2") (pintype "passive"))
    )
    (net (code "121") (name "unconnected-(X1D-1-PadG3)") (class "Default")
      (node (ref "X1") (pin "G3") (pinfunction "1_G3") (pintype "passive"))
    )
    (net (code "122") (name "unconnected-(X1E-1-PadG4)") (class "Default")
      (node (ref "X1") (pin "G4") (pinfunction "1_G4") (pintype "passive"))
    )
    (net (code "123") (name "unconnected-(X2-Pad1)") (class "Default")
      (node (ref "X2") (pin "1") (pinfunction "1_1") (pintype "passive"))
    )
    (net (code "124") (name "unconnected-(X2-Pad3)") (class "Default")
      (node (ref "X2") (pin "3") (pinfunction "3_3") (pintype "passive"))
    )
    (net (code "125") (name "unconnected-(X2-Pad5)") (class "Default")
      (node (ref "X2") (pin "5") (pinfunction "5_5") (pintype "passive"))
    )
    (net (code "126") (name "unconnected-(X2-Pad7)") (class "Default")
      (node (ref "X2") (pin "7") (pinfunction "7_7") (pintype "passive"))
    )
    (net (code "127") (name "unconnected-(X2B-1-PadG1)") (class "Default")
      (node (ref "X2") (pin "G1") (pinfunction "1_G1") (pintype "passive"))
    )
    (net (code "128") (name "unconnected-(X2C-1-PadG2)") (class "Default")
      (node (ref "X2") (pin "G2") (pinfunction "1_G2") (pintype "passive"))
    )
    (net (code "129") (name "unconnected-(X2D-1-PadG3)") (class "Default")
      (node (ref "X2") (pin "G3") (pinfunction "1_G3") (pintype "passive"))
    )
    (net (code "130") (name "unconnected-(X2E-1-PadG4)") (class "Default")
      (node (ref "X2") (pin "G4") (pinfunction "1_G4") (pintype "passive"))
    )
    (net (code "131") (name "unconnected-(X3-Pad4)") (class "Default")
      (node (ref "X3") (pin "4") (pinfunction "4_4") (pintype "passive"))
    )
    (net (code "132") (name "unconnected-(X3-Pad5)") (class "Default")
      (node (ref "X3") (pin "5") (pinfunction "5_5") (pintype "passive"))
    )
    (net (code "133") (name "unconnected-(X3B-1-PadG1)") (class "Default")
      (node (ref "X3") (pin "G1") (pinfunction "1_G1") (pintype "passive"))
    )
    (net (code "134") (name "unconnected-(X3C-1-PadG2)") (class "Default")
      (node (ref "X3") (pin "G2") (pinfunction "1_G2") (pintype "passive"))
    )
    (net (code "135") (name "unconnected-(X3D-1-PadG3)") (class "Default")
      (node (ref "X3") (pin "G3") (pinfunction "1_G3") (pintype "passive"))
    )
    (net (code "136") (name "unconnected-(X3E-1-PadG4)") (class "Default")
      (node (ref "X3") (pin "G4") (pinfunction "1_G4") (pintype "passive"))
    )
  )
)
